# 1-Schematic_main_project_bg-butwal.net
KiCad netlist of a schematic drawn in EasyEDA
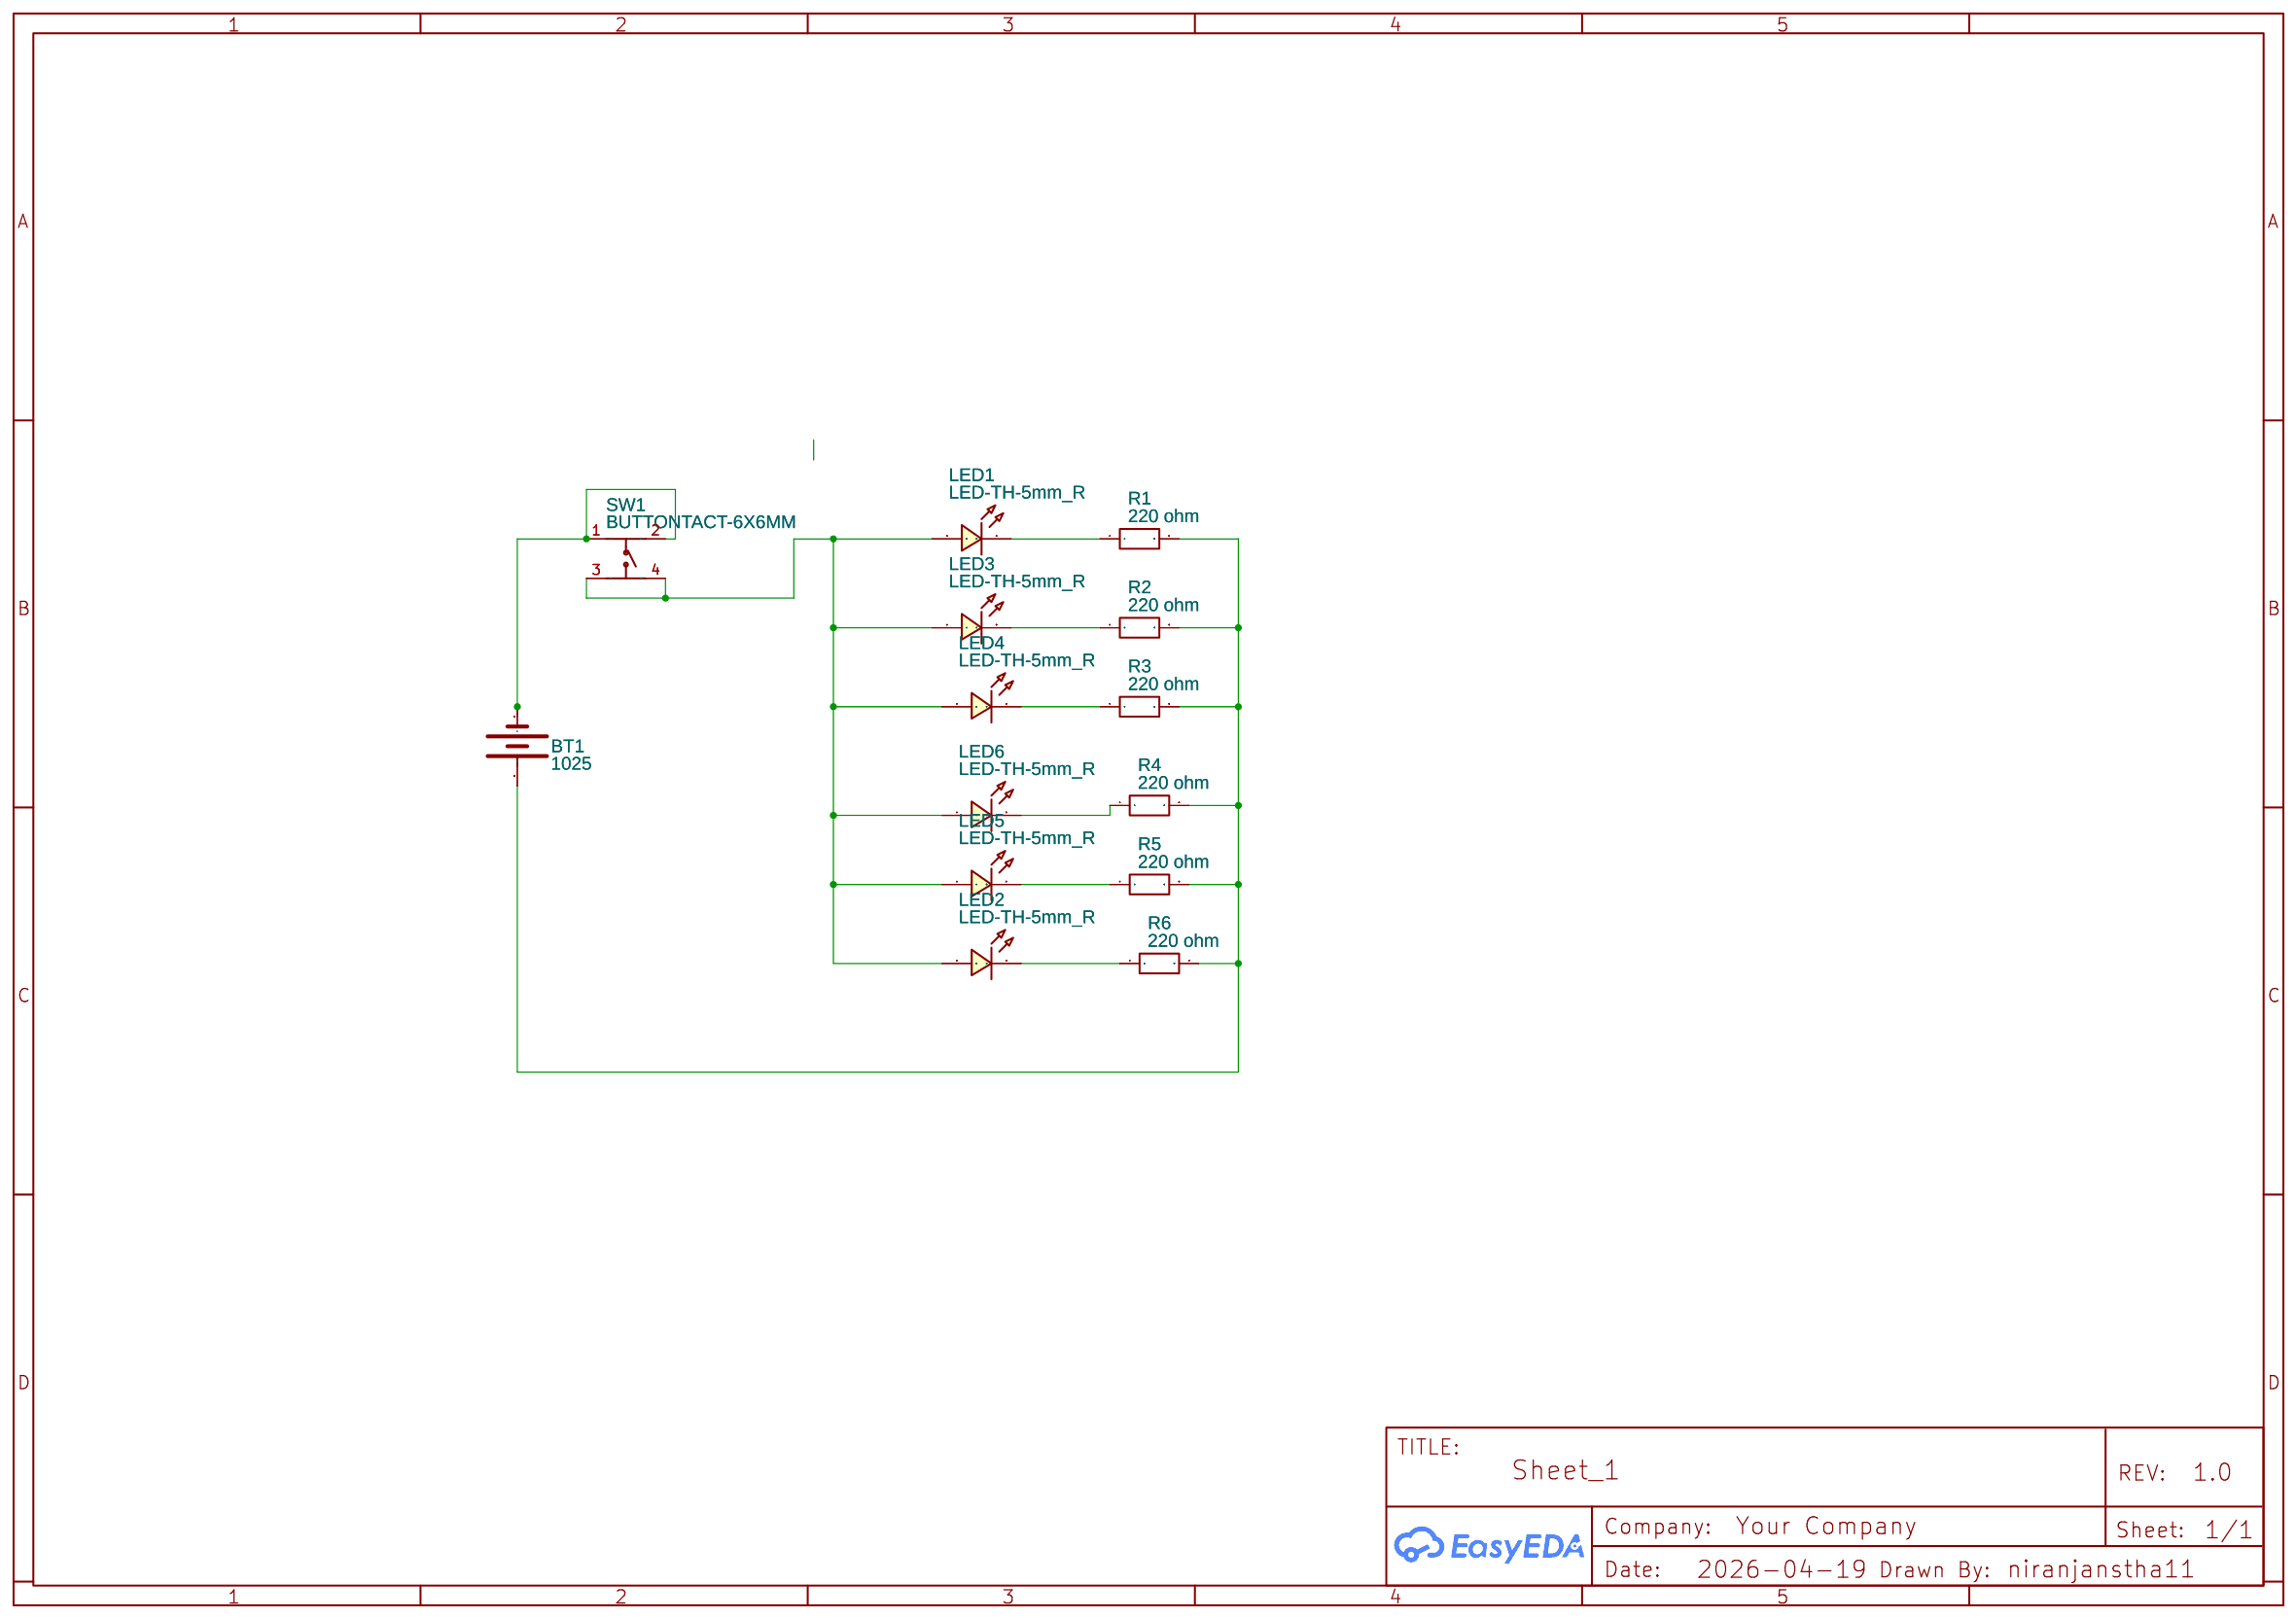
[diagram p0: schematic sheet]

(export (version "E")
  (design (tool "Eeschema 10.0.6"))
  (components
    (comp (ref "BT1")
      (value "1025")
      (fields (field (name "Manufacturer") "Keystone"))
      (libsource (lib "") (part "1025"))
    )
    (comp (ref "LED1")
      (value "LED-TH-5mm_R")
      (fields
        (field (name "Manufacturer Part") "333-2SURD/S530-A3")
        (field (name "Manufacturer") "EVERLIGHT(台湾亿光)")
      )
      (libsource (lib "") (part "LED-TH-5mm_R"))
    )
    (comp (ref "LED2")
      (value "LED-TH-5mm_R")
      (fields
        (field (name "Manufacturer Part") "333-2SURD/S530-A3")
        (field (name "Manufacturer") "EVERLIGHT(台湾亿光)")
      )
      (libsource (lib "") (part "LED-TH-5mm_R"))
    )
    (comp (ref "LED3")
      (value "LED-TH-5mm_R")
      (fields
        (field (name "Manufacturer Part") "333-2SURD/S530-A3")
        (field (name "Manufacturer") "EVERLIGHT(台湾亿光)")
      )
      (libsource (lib "") (part "LED-TH-5mm_R"))
    )
    (comp (ref "LED4")
      (value "LED-TH-5mm_R")
      (fields
        (field (name "Manufacturer Part") "333-2SURD/S530-A3")
        (field (name "Manufacturer") "EVERLIGHT(台湾亿光)")
      )
      (libsource (lib "") (part "LED-TH-5mm_R"))
    )
    (comp (ref "LED5")
      (value "LED-TH-5mm_R")
      (fields
        (field (name "Manufacturer Part") "333-2SURD/S530-A3")
        (field (name "Manufacturer") "EVERLIGHT(台湾亿光)")
      )
      (libsource (lib "") (part "LED-TH-5mm_R"))
    )
    (comp (ref "LED6")
      (value "LED-TH-5mm_R")
      (fields
        (field (name "Manufacturer Part") "333-2SURD/S530-A3")
        (field (name "Manufacturer") "EVERLIGHT(台湾亿光)")
      )
      (libsource (lib "") (part "LED-TH-5mm_R"))
    )
    (comp (ref "R1") (value "220 ohm") (libsource (lib "") (part "R_0603_EU")))
    (comp (ref "R2") (value "220 ohm") (libsource (lib "") (part "R_0603_EU")))
    (comp (ref "R3") (value "220 ohm") (libsource (lib "") (part "R_0603_EU")))
    (comp (ref "R4") (value "220 ohm") (libsource (lib "") (part "R_0603_EU")))
    (comp (ref "R5") (value "220 ohm") (libsource (lib "") (part "R_0603_EU")))
    (comp (ref "R6") (value "220 ohm") (libsource (lib "") (part "R_0603_EU")))
    (comp (ref "SW1")
      (value "BUTTONTACT-6X6MM")
      (fields (field (name "Manufacturer Part") "Buttontact-6x6mm"))
      (libsource (lib "") (part "BUTTONTACT-6X6MM"))
    )
  )
  (nets
    (net (code "1") (name "Net-(BT1-+)") (class "Default")
      (node (ref "BT1") (pin "1") (pinfunction "+_1") (pintype "passive"))
      (node (ref "R1") (pin "2") (pinfunction "2_2") (pintype "unspecified"))
      (node (ref "R2") (pin "2") (pinfunction "2_2") (pintype "unspecified"))
      (node (ref "R3") (pin "2") (pinfunction "2_2") (pintype "unspecified"))
      (node (ref "R4") (pin "2") (pinfunction "2_2") (pintype "unspecified"))
      (node (ref "R5") (pin "2") (pinfunction "2_2") (pintype "unspecified"))
      (node (ref "R6") (pin "2") (pinfunction "2_2") (pintype "unspecified"))
    )
    (net (code "2") (name "Net-(BT1--)") (class "Default")
      (node (ref "BT1") (pin "2") (pinfunction "-_2") (pintype "passive"))
      (node (ref "SW1") (pin "1") (pinfunction "A_1") (pintype "unspecified"))
      (node (ref "SW1") (pin "2") (pinfunction "B_2") (pintype "unspecified"))
    )
    (net (code "3") (name "Net-(LED1-Pad2)") (class "Default")
      (node (ref "LED1") (pin "2") (pinfunction "2_2") (pintype "unspecified"))
      (node (ref "R1") (pin "1") (pinfunction "1_1") (pintype "unspecified"))
    )
    (net (code "4") (name "Net-(LED2-Pad2)") (class "Default")
      (node (ref "LED2") (pin "2") (pinfunction "2_2") (pintype "unspecified"))
      (node (ref "R6") (pin "1") (pinfunction "1_1") (pintype "unspecified"))
    )
    (net (code "5") (name "Net-(LED3-Pad2)") (class "Default")
      (node (ref "LED3") (pin "2") (pinfunction "2_2") (pintype "unspecified"))
      (node (ref "R2") (pin "1") (pinfunction "1_1") (pintype "unspecified"))
    )
    (net (code "6") (name "Net-(LED4-Pad2)") (class "Default")
      (node (ref "LED4") (pin "2") (pinfunction "2_2") (pintype "unspecified"))
      (node (ref "R3") (pin "1") (pinfunction "1_1") (pintype "unspecified"))
    )
    (net (code "7") (name "Net-(LED5-Pad2)") (class "Default")
      (node (ref "LED5") (pin "2") (pinfunction "2_2") (pintype "unspecified"))
      (node (ref "R5") (pin "1") (pinfunction "1_1") (pintype "unspecified"))
    )
    (net (code "8") (name "Net-(LED6-Pad2)") (class "Default")
      (node (ref "LED6") (pin "2") (pinfunction "2_2") (pintype "unspecified"))
      (node (ref "R4") (pin "1") (pinfunction "1_1") (pintype "unspecified"))
    )
    (net (code "9") (name "Net-(SW1-C)") (class "Default")
      (node (ref "LED1") (pin "1") (pinfunction "1_1") (pintype "unspecified"))
      (node (ref "LED2") (pin "1") (pinfunction "1_1") (pintype "unspecified"))
      (node (ref "LED3") (pin "1") (pinfunction "1_1") (pintype "unspecified"))
      (node (ref "LED4") (pin "1") (pinfunction "1_1") (pintype "unspecified"))
      (node (ref "LED5") (pin "1") (pinfunction "1_1") (pintype "unspecified"))
      (node (ref "LED6") (pin "1") (pinfunction "1_1") (pintype "unspecified"))
      (node (ref "SW1") (pin "3") (pinfunction "C_3") (pintype "unspecified"))
      (node (ref "SW1") (pin "4") (pinfunction "D_4") (pintype "unspecified"))
    )
  )
)
